# base.net
KiCad netlist of a schematic drawn in Altium Designer
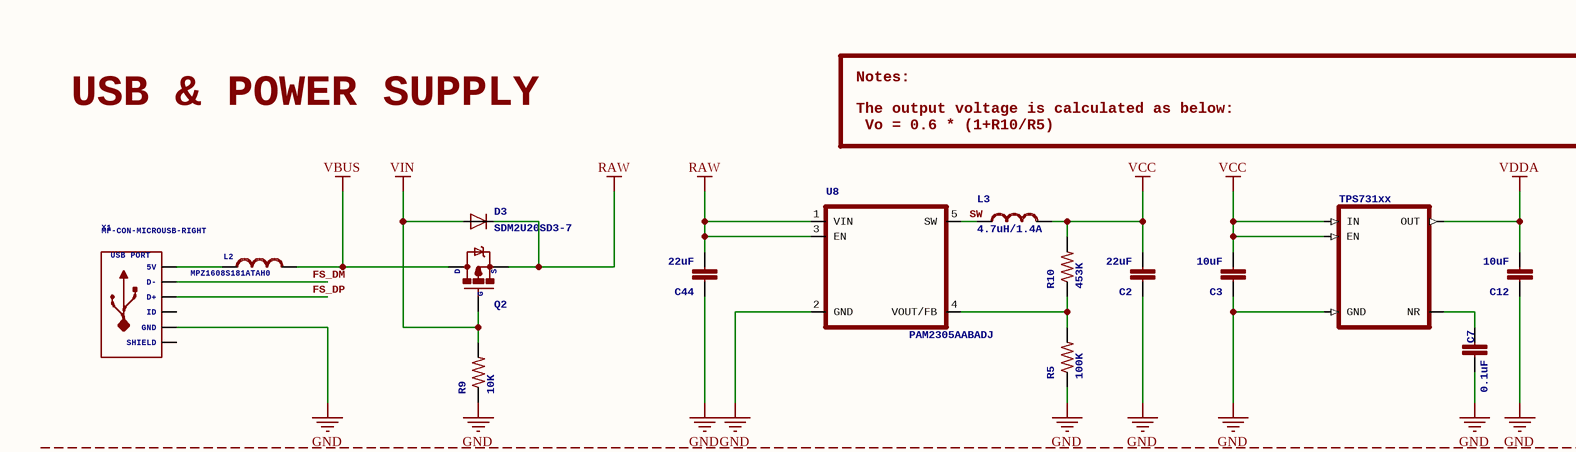
[diagram p0: base.SchDoc, top left]
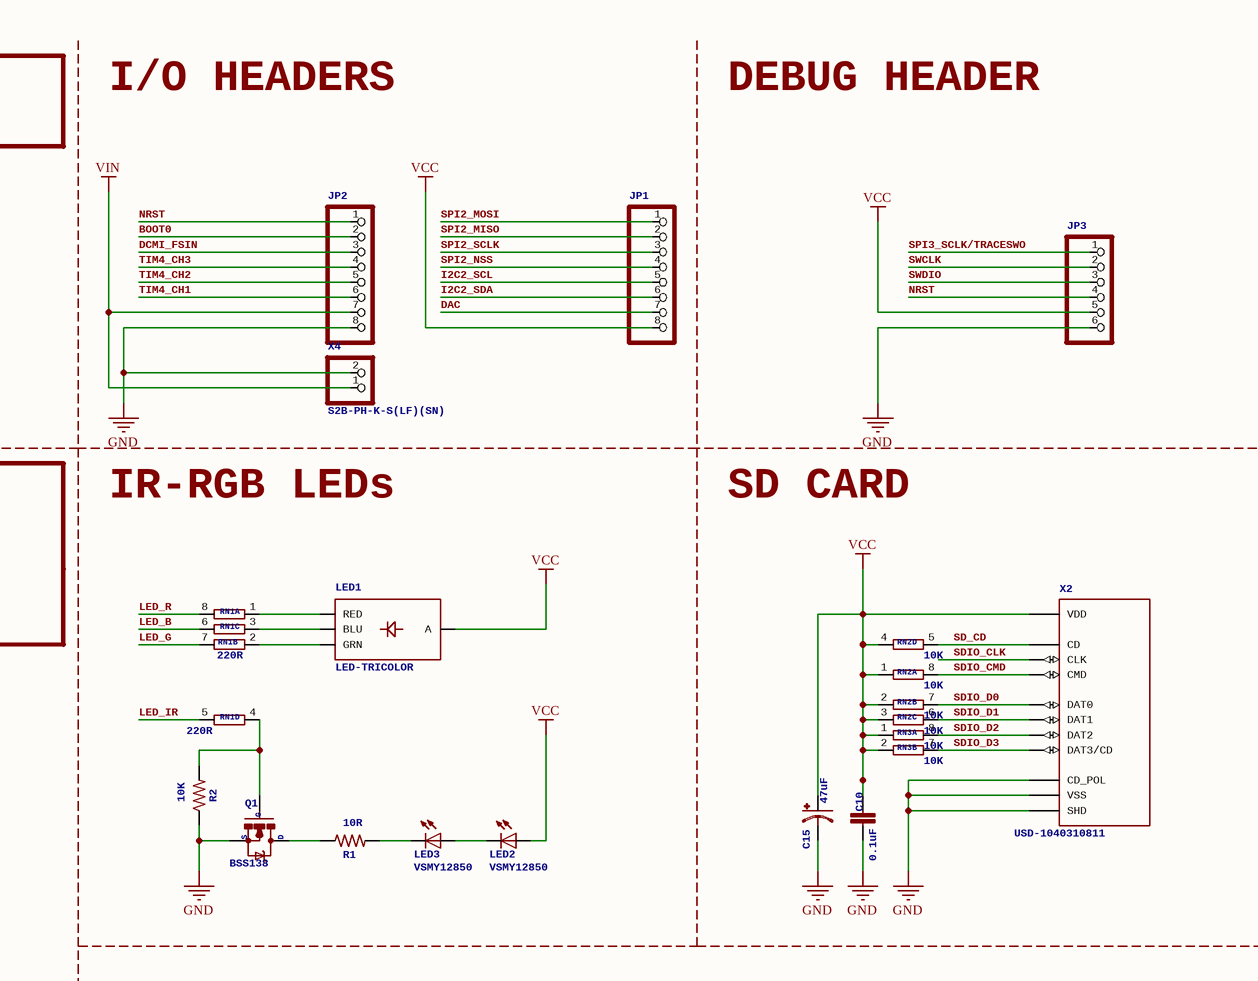
[diagram p1: base.SchDoc, top right]
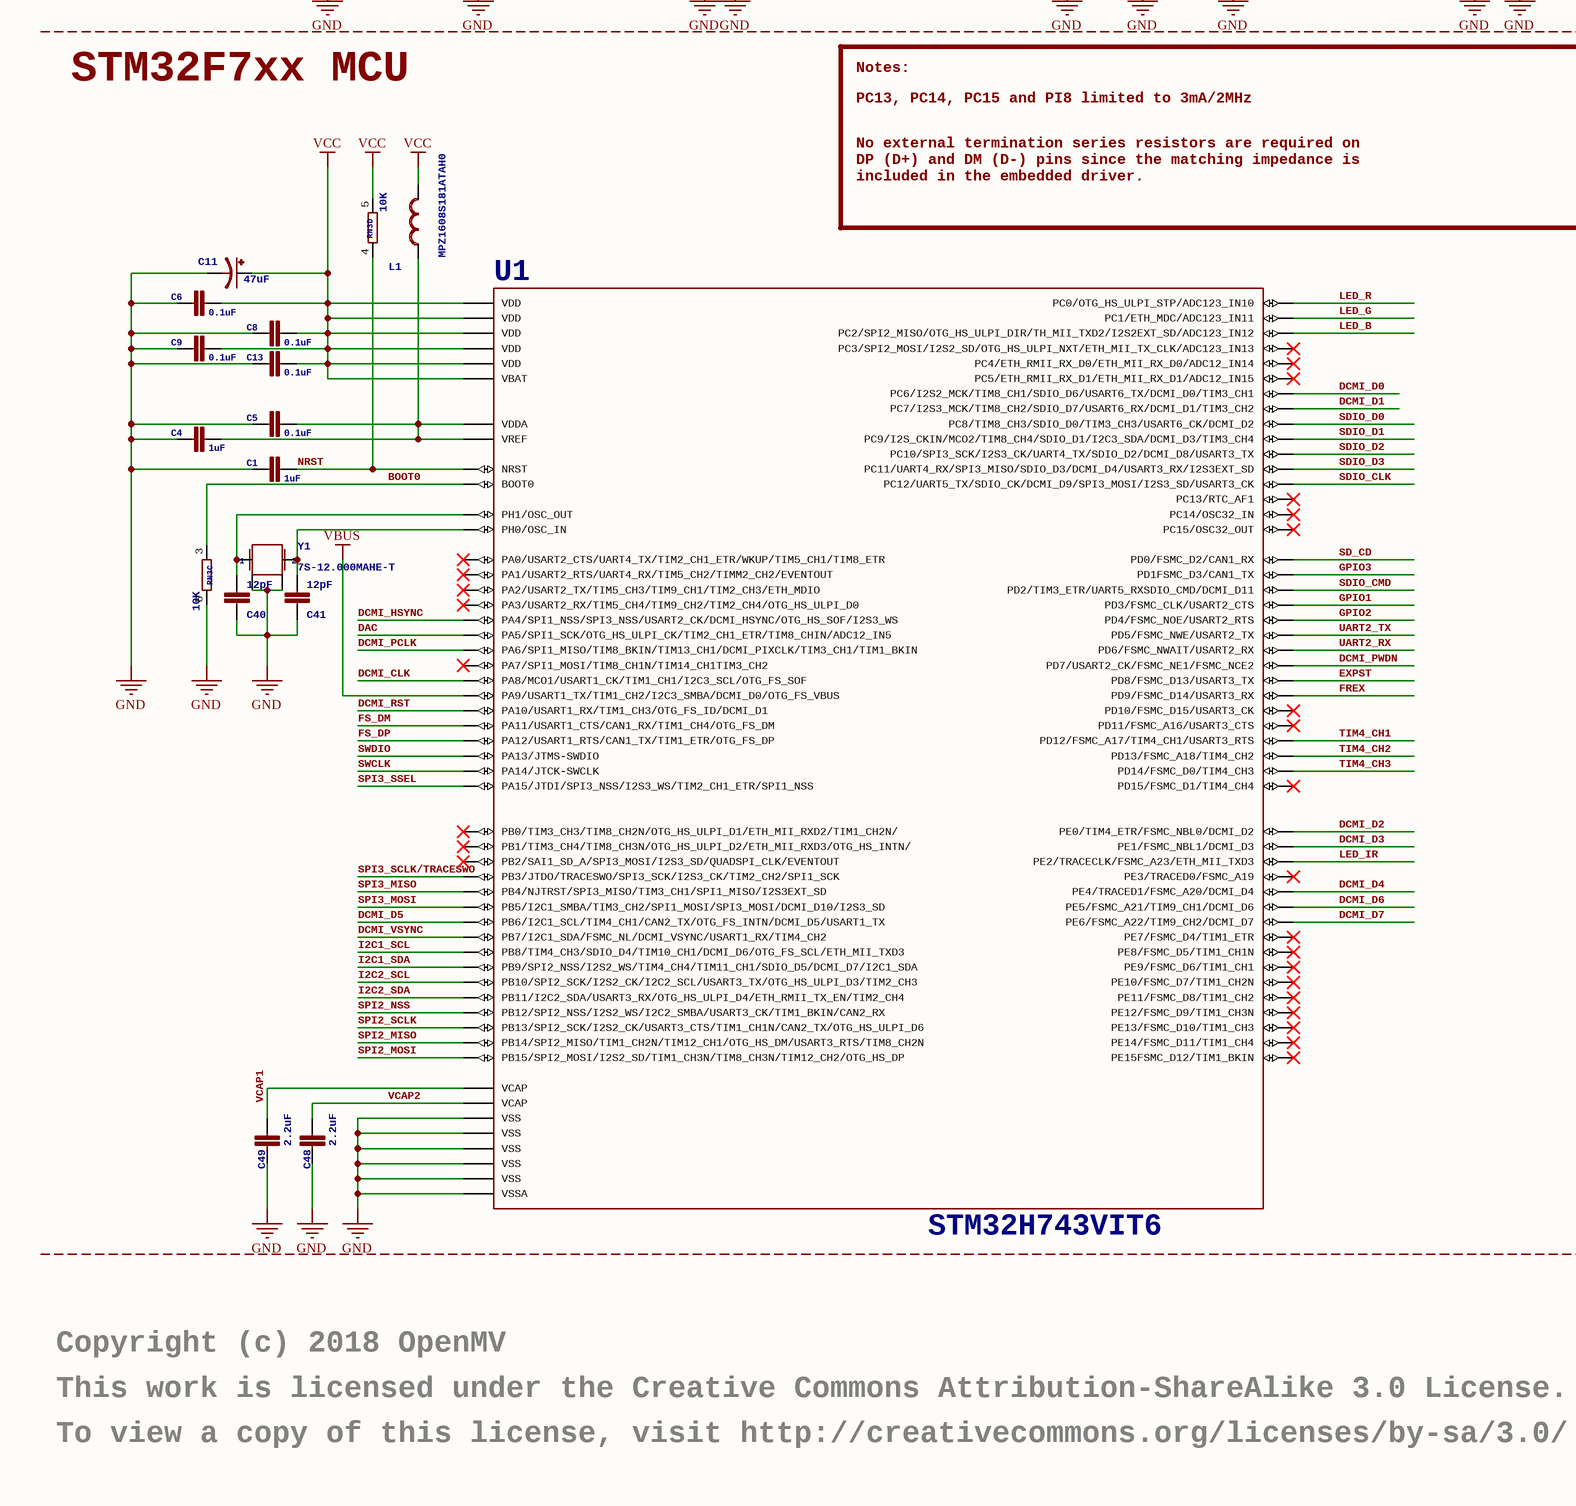
[diagram p2: base.SchDoc, bottom left]
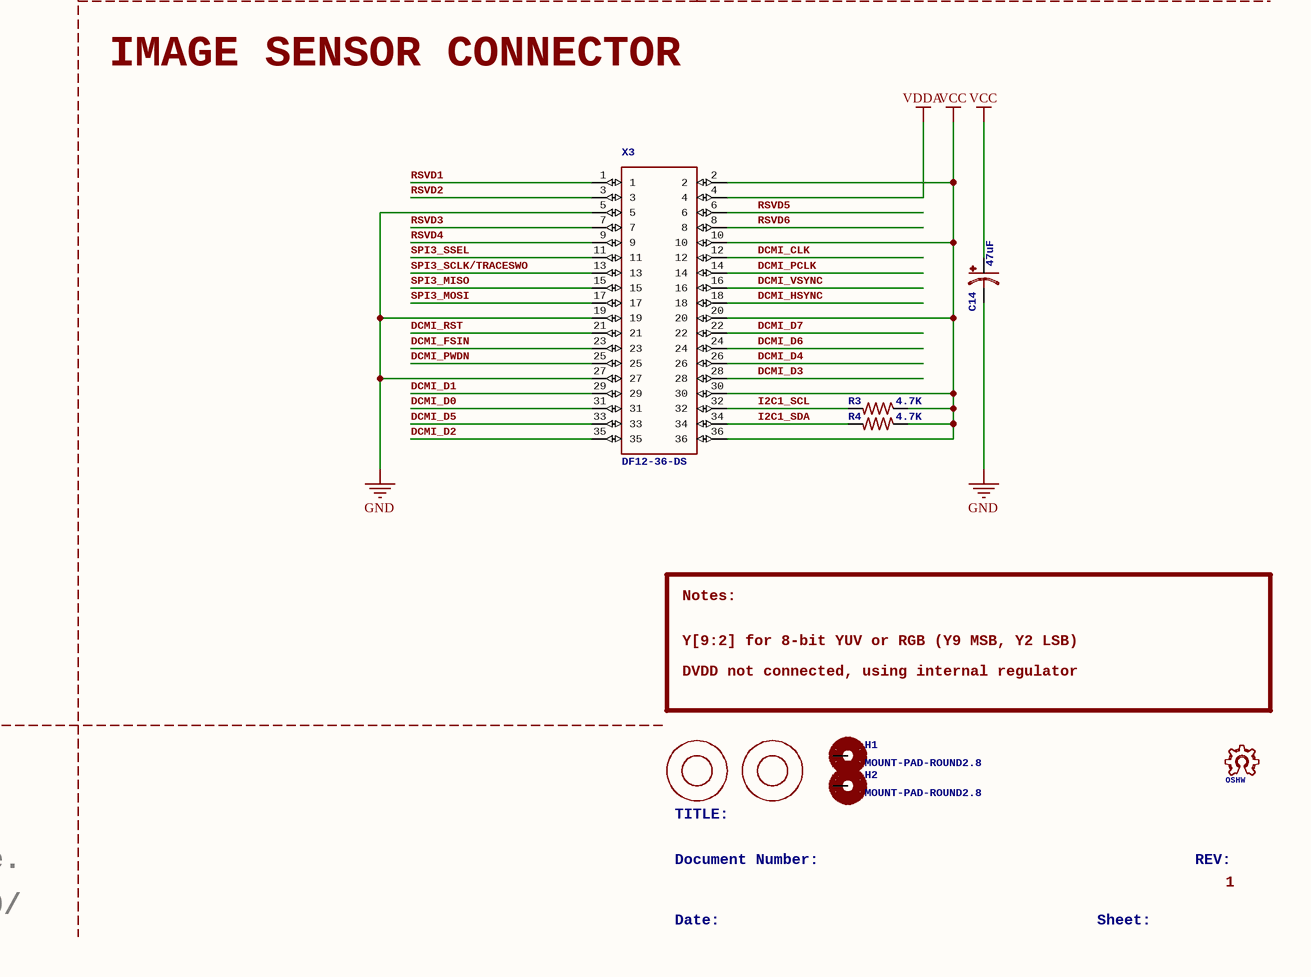
[diagram p3: base.SchDoc, bottom right]

(export (version "E")
  (design (tool "Eeschema 10.0.6"))
  (components
    (comp (ref "C1")
      (value "1uF")
      (footprint "0603-CAP")
      (description "CapacitorStandard 0603 ceramic capacitor, and 0.1\" leaded capacitor.")
      (libsource (lib "") (part "CAP0603-CAP_1"))
    )
    (comp (ref "C2")
      (value "22uF")
      (footprint "0805")
      (description "CapacitorStandard 0603 ceramic capacitor, and 0.1\" leaded capacitor.")
      (libsource (lib "sfe") (part "CAP0805"))
    )
    (comp (ref "C3")
      (value "10uF")
      (footprint "0805")
      (description "CapacitorStandard 0603 ceramic capacitor, and 0.1\" leaded capacitor.")
      (libsource (lib "sfe") (part "CAP0805"))
    )
    (comp (ref "C4")
      (value "1uF")
      (footprint "0603-CAP")
      (description "CapacitorStandard 0603 ceramic capacitor, and 0.1\" leaded capacitor.")
      (libsource (lib "") (part "CAP0603-CAP_1"))
    )
    (comp (ref "C5")
      (value "0.1uF")
      (footprint "0603-CAP")
      (description "CapacitorStandard 0603 ceramic capacitor, and 0.1\" leaded capacitor.")
      (libsource (lib "") (part "CAP0603-CAP_1"))
    )
    (comp (ref "C6")
      (value "0.1uF")
      (footprint "0603-CAP")
      (description "CapacitorStandard 0603 ceramic capacitor, and 0.1\" leaded capacitor.")
      (libsource (lib "") (part "CAP0603-CAP_1"))
    )
    (comp (ref "C7")
      (value "0.1uF")
      (footprint "0603-CAP")
      (description "CapacitorStandard 0603 ceramic capacitor, and 0.1\" leaded capacitor.")
      (libsource (lib "sfe") (part "CAP0603-CAP"))
    )
    (comp (ref "C8")
      (value "0.1uF")
      (footprint "0603-CAP")
      (description "CapacitorStandard 0603 ceramic capacitor, and 0.1\" leaded capacitor.")
      (libsource (lib "") (part "CAP0603-CAP_1"))
    )
    (comp (ref "C9")
      (value "0.1uF")
      (footprint "0603-CAP")
      (description "CapacitorStandard 0603 ceramic capacitor, and 0.1\" leaded capacitor.")
      (libsource (lib "") (part "CAP0603-CAP_1"))
    )
    (comp (ref "C10")
      (value "0.1uF")
      (footprint "0603-CAP")
      (description "CapacitorStandard 0603 ceramic capacitor, and 0.1\" leaded capacitor.")
      (libsource (lib "sfe") (part "CAP0603-CAP"))
    )
    (comp (ref "C11") (value "47uF") (footprint "EIA3216") (libsource (lib "") (part "CAP_POL1206_1")))
    (comp (ref "C12")
      (value "10uF")
      (footprint "0805")
      (description "CapacitorStandard 0603 ceramic capacitor, and 0.1\" leaded capacitor.")
      (libsource (lib "sfe") (part "CAP0805"))
    )
    (comp (ref "C13")
      (value "0.1uF")
      (footprint "0603-CAP")
      (description "CapacitorStandard 0603 ceramic capacitor, and 0.1\" leaded capacitor.")
      (libsource (lib "") (part "CAP0603-CAP_1"))
    )
    (comp (ref "C14") (value "47uF") (footprint "EIA3216") (libsource (lib "sfe") (part "CAP_POL1206")))
    (comp (ref "C15") (value "47uF") (footprint "EIA3216") (libsource (lib "sfe") (part "CAP_POL1206")))
    (comp (ref "C40")
      (value "12pF")
      (footprint "0603-CAP")
      (description "CapacitorStandard 0603 ceramic capacitor, and 0.1\" leaded capacitor.")
      (libsource (lib "") (part "CAP0603-CAP_2"))
    )
    (comp (ref "C41")
      (value "12pF")
      (footprint "0603-CAP")
      (description "CapacitorStandard 0603 ceramic capacitor, and 0.1\" leaded capacitor.")
      (libsource (lib "") (part "CAP0603-CAP_2"))
    )
    (comp (ref "C44")
      (value "22uF")
      (footprint "0805")
      (description "CapacitorStandard 0603 ceramic capacitor, and 0.1\" leaded capacitor.")
      (libsource (lib "sfe") (part "CAP0805"))
    )
    (comp (ref "C48")
      (value "2.2uF")
      (footprint "0603-CAP")
      (description "CapacitorStandard 0603 ceramic capacitor, and 0.1\" leaded capacitor.")
      (libsource (lib "sfe") (part "CAP0603-CAP"))
    )
    (comp (ref "C49")
      (value "2.2uF")
      (footprint "0603-CAP")
      (description "CapacitorStandard 0603 ceramic capacitor, and 0.1\" leaded capacitor.")
      (libsource (lib "sfe") (part "CAP0603-CAP"))
    )
    (comp (ref "D3") (value "SDM2U20SD3-7") (footprint "SOD-323") (libsource (lib "sfe") (part "DIODESOD")))
    (comp (ref "H1")
      (value "MOUNT-PAD-ROUND2.8")
      (footprint "2,8-PAD")
      (description "MOUNTING PAD, round")
      (libsource (lib "holes") (part "MOUNT-PAD-ROUND2.8"))
    )
    (comp (ref "H2")
      (value "MOUNT-PAD-ROUND2.8")
      (footprint "2,8-PAD")
      (description "MOUNTING PAD, round")
      (libsource (lib "holes") (part "MOUNT-PAD-ROUND2.8"))
    )
    (comp (ref "JP1")
      (value "PINHD-1X8")
      (footprint "1X08")
      (description "PIN HEADER")
      (fields (field (name "LIBRARYNAME") "pinhead"))
      (libsource (lib "pinhead") (part "PINHD-1X8"))
    )
    (comp (ref "JP2")
      (value "PINHD-1X8")
      (footprint "1X08")
      (description "PIN HEADER")
      (fields (field (name "LIBRARYNAME") "pinhead"))
      (libsource (lib "pinhead") (part "PINHD-1X8"))
    )
    (comp (ref "JP3")
      (value "PINHD-1X6")
      (footprint "1X06")
      (description "PIN HEADER")
      (fields (field (name "LIBRARYNAME") "pinhead"))
      (libsource (lib "pinhead") (part "PINHD-1X6"))
    )
    (comp (ref "L1")
      (value "MPZ1608S181ATAH0")
      (footprint "0603")
      (libsource (lib "sfe") (part "INDUCTOR0603"))
    )
    (comp (ref "L2")
      (value "MPZ1608S181ATAH0")
      (footprint "0603")
      (libsource (lib "sfe") (part "INDUCTOR0603"))
    )
    (comp (ref "L3") (value "4.7uH/1.4A") (footprint "1007") (libsource (lib "sfe") (part "INDUCTOR1007")))
    (comp (ref "LED1")
      (value "LED-TRICOLOR")
      (footprint "LED-TRICOLOR-SMD-MF")
      (libsource (lib "sfe") (part "LED-TRICOLOR"))
    )
    (comp (ref "LED2") (value "VSMY12850") (footprint "LED-1206") (libsource (lib "sfe") (part "LED1206")))
    (comp (ref "LED3") (value "VSMY12850") (footprint "LED-1206") (libsource (lib "sfe") (part "LED1206")))
    (comp (ref "LOGO1")
      (value "OSHW_LOGO_FILLX0100-NT")
      (footprint "OSHW_FILLX100_NOTEXT")
      (fields (field (name "OSHW") "OSHW") (field (name "LIBRARYNAME") "iofault"))
      (libsource (lib "iofault") (part "OSHW_LOGO_FILLX0100-NT"))
    )
    (comp (ref "M1")
      (value "9774030243R")
      (footprint "9774030151R")
      (libsource (lib "STANDOFFS") (part "9774030151R"))
    )
    (comp (ref "M2")
      (value "9774030243R")
      (footprint "9774030151R")
      (libsource (lib "STANDOFFS") (part "9774030151R"))
    )
    (comp (ref "Q1")
      (value "BSS138")
      (footprint "SOT23-3")
      (fields (field (name "D") "D") (field (name "S") "S") (field (name "G") "G"))
      (libsource (lib "sfe") (part "MOSFET-NCHANNELSMD"))
    )
    (comp (ref "Q2")
      (value "Si2301BDS")
      (footprint "SOT23-3")
      (fields (field (name "D") "D") (field (name "S") "S") (field (name "G") "G"))
      (libsource (lib "sfe") (part "MOSFET-PCHANNELSMD"))
    )
    (comp (ref "R1")
      (value "10R")
      (footprint "0603-RES")
      (description "ResistorBasic schematic elements and footprints for 0603, 1206, and PTH resistors.")
      (libsource (lib "sfe") (part "RESISTOR0603-RES"))
    )
    (comp (ref "R2")
      (value "10K")
      (footprint "0603-RES")
      (description "ResistorBasic schematic elements and footprints for 0603, 1206, and PTH resistors.")
      (libsource (lib "sfe") (part "RESISTOR0603-RES"))
    )
    (comp (ref "R3")
      (value "4.7K")
      (footprint "0603-RES")
      (description "ResistorBasic schematic elements and footprints for 0603, 1206, and PTH resistors.")
      (libsource (lib "sfe") (part "RESISTOR0603-RES"))
    )
    (comp (ref "R4")
      (value "4.7K")
      (footprint "0603-RES")
      (description "ResistorBasic schematic elements and footprints for 0603, 1206, and PTH resistors.")
      (libsource (lib "sfe") (part "RESISTOR0603-RES"))
    )
    (comp (ref "R5")
      (value "100K")
      (footprint "0603-RES")
      (description "ResistorBasic schematic elements and footprints for 0603, 1206, and PTH resistors.")
      (libsource (lib "sfe") (part "RESISTOR0603-RES"))
    )
    (comp (ref "R9")
      (value "10K")
      (footprint "0603-RES")
      (description "ResistorBasic schematic elements and footprints for 0603, 1206, and PTH resistors.")
      (libsource (lib "sfe") (part "RESISTOR0603-RES"))
    )
    (comp (ref "R10")
      (value "453K")
      (footprint "0603-RES")
      (description "ResistorBasic schematic elements and footprints for 0603, 1206, and PTH resistors.")
      (libsource (lib "sfe") (part "RESISTOR0603-RES"))
    )
    (comp (ref "RN1")
      (value "220R")
      (footprint "EXBV8V")
      (description "Array Chip Resistor   Source: RS Component / Phycomp")
      (fields (field (name "LIBRARYNAME") "resistor-dil"))
      (libsource (lib "resistor-dil") (part "4R-NEXBV8V"))
    )
    (comp (ref "RN2")
      (value "10K")
      (footprint "EXBV8V")
      (description "Array Chip Resistor   Source: RS Component / Phycomp")
      (fields (field (name "LIBRARYNAME") "resistor-dil"))
      (libsource (lib "resistor-dil") (part "4R-NEXBV8V"))
    )
    (comp (ref "RN3")
      (value "10K")
      (footprint "EXBV8V")
      (description "Array Chip Resistor   Source: RS Component / Phycomp")
      (fields (field (name "LIBRARYNAME") "resistor-dil"))
      (libsource (lib "resistor-dil") (part "4R-NEXBV8V"))
    )
    (comp (ref "U1")
      (value "STM32H743VIT6")
      (footprint "LQFP100")
      (libsource (lib "stm32") (part "STM32F746LQFP100"))
    )
    (comp (ref "U5")
      (value "TPS731XX")
      (footprint "SOT23-5")
      (fields (field (name "TPS731XX") "TPS731xx") (field (name "LIBRARYNAME") "mux"))
      (libsource (lib "mux") (part "TPS731XX"))
    )
    (comp (ref "U8")
      (value "PAM2305AABADJ")
      (footprint "TSOT25")
      (libsource (lib "regulators") (part "PAM2305AAB330"))
    )
    (comp (ref "X1")
      (value "MF-CON-MICROUSB-RIGHT")
      (footprint "MICROUSB-RIGHT")
      (fields
        (field (name "USBPORT") "USB PORT")
        (field (name "5V") "5V")
        (field (name "D-") "D-")
        (field (name "D+") "D+")
        (field (name "ID") "ID")
        (field (name "GND") "GND")
        (field (name "SHIELD") "SHIELD")
      )
      (libsource (lib "MF_Connectors") (part "USB_MICRO_RIGHT"))
    )
    (comp (ref "X2")
      (value "USD-1040310811")
      (footprint "1040310811")
      (libsource (lib "molex") (part "USD-1040310811"))
    )
    (comp (ref "X3")
      (value "DF12-36-DS")
      (footprint "DF12-36-DS")
      (libsource (lib "DF12") (part "DF12-36-DS"))
    )
    (comp (ref "X4")
      (value "S2B-PH-K-S(LF)(SN)")
      (footprint "JST-PH-2-THM-RA")
      (fields (field (name "LIBRARYNAME") "adafruit-updated"))
      (libsource (lib "adafruit-updated") (part "JST_2PIN-THM-RA"))
    )
    (comp (ref "Y1")
      (value "7S-12.000MAHE-T")
      (footprint "CRYSTAL-2.5X2.0")
      (description "CrystalsVarious standard crystals. Proven footprints. Spark Fun Electronics SKU : COM-00534")
      (fields (field (name "1") "1") (field (name "2") "2") (field (name "LIBRARYNAME") "mux"))
      (libsource (lib "mux") (part "CRYSTAL2.5X2.0"))
    )
  )
  (nets
    (net (code "1") (name "/BOOT0") (class "Default")
      (node (ref "JP2") (pin "2") (pinfunction "2_2") (pintype "passive"))
      (node (ref "RN3") (pin "3") (pinfunction "1_3") (pintype "passive"))
      (node (ref "U1") (pin "94") (pinfunction "BOOT0_94") (pintype "bidirectional"))
    )
    (net (code "2") (name "/DAC") (class "Default")
      (node (ref "JP1") (pin "7") (pinfunction "7_7") (pintype "passive"))
      (node (ref "U1") (pin "29") (pinfunction "PA5/SPI1_SCK/OTG_HS_ULPI_CK/TIM2_CH1_ETR/TIM8_CHIN/ADC12_IN5_29") (pintype "bidirectional"))
    )
    (net (code "3") (name "/DCMI_CLK") (class "Default")
      (node (ref "U1") (pin "67") (pinfunction "PA8/MCO1/USART1_CK/TIM1_CH1/I2C3_SCL/OTG_FS_SOF_67") (pintype "bidirectional"))
      (node (ref "X3") (pin "12") (pinfunction "12_12") (pintype "bidirectional"))
    )
    (net (code "4") (name "/DCMI_D0") (class "Default")
      (node (ref "U1") (pin "63") (pinfunction "PC6/I2S2_MCK/TIM8_CH1/SDIO_D6/USART6_TX/DCMI_D0/TIM3_CH1_63") (pintype "bidirectional"))
      (node (ref "X3") (pin "31") (pinfunction "31_31") (pintype "bidirectional"))
    )
    (net (code "5") (name "/DCMI_D1") (class "Default")
      (node (ref "U1") (pin "64") (pinfunction "PC7/I2S3_MCK/TIM8_CH2/SDIO_D7/USART6_RX/DCMI_D1/TIM3_CH2_64") (pintype "bidirectional"))
      (node (ref "X3") (pin "29") (pinfunction "29_29") (pintype "bidirectional"))
    )
    (net (code "6") (name "/DCMI_D2") (class "Default")
      (node (ref "U1") (pin "97") (pinfunction "PE0/TIM4_ETR/FSMC_NBL0/DCMI_D2_97") (pintype "bidirectional"))
      (node (ref "X3") (pin "35") (pinfunction "35_35") (pintype "bidirectional"))
    )
    (net (code "7") (name "/DCMI_D3") (class "Default")
      (node (ref "U1") (pin "98") (pinfunction "PE1/FSMC_NBL1/DCMI_D3_98") (pintype "bidirectional"))
      (node (ref "X3") (pin "28") (pinfunction "28_28") (pintype "bidirectional"))
    )
    (net (code "8") (name "/DCMI_D4") (class "Default")
      (node (ref "U1") (pin "3") (pinfunction "PE4/TRACED1/FSMC_A20/DCMI_D4_3") (pintype "bidirectional"))
      (node (ref "X3") (pin "26") (pinfunction "26_26") (pintype "bidirectional"))
    )
    (net (code "9") (name "/DCMI_D5") (class "Default")
      (node (ref "U1") (pin "92") (pinfunction "PB6/I2C1_SCL/TIM4_CH1/CAN2_TX/OTG_FS_INTN/DCMI_D5/USART1_TX_92") (pintype "bidirectional"))
      (node (ref "X3") (pin "33") (pinfunction "33_33") (pintype "bidirectional"))
    )
    (net (code "10") (name "/DCMI_D6") (class "Default")
      (node (ref "U1") (pin "4") (pinfunction "PE5/FSMC_A21/TIM9_CH1/DCMI_D6_4") (pintype "bidirectional"))
      (node (ref "X3") (pin "24") (pinfunction "24_24") (pintype "bidirectional"))
    )
    (net (code "11") (name "/DCMI_D7") (class "Default")
      (node (ref "U1") (pin "5") (pinfunction "PE6/FSMC_A22/TIM9_CH2/DCMI_D7_5") (pintype "bidirectional"))
      (node (ref "X3") (pin "22") (pinfunction "22_22") (pintype "bidirectional"))
    )
    (net (code "12") (name "/DCMI_FSIN") (class "Default")
      (node (ref "JP2") (pin "3") (pinfunction "3_3") (pintype "passive"))
      (node (ref "X3") (pin "23") (pinfunction "23_23") (pintype "bidirectional"))
    )
    (net (code "13") (name "/DCMI_HSYNC") (class "Default")
      (node (ref "U1") (pin "28") (pinfunction "PA4/SPI1_NSS/SPI3_NSS/USART2_CK/DCMI_HSYNC/OTG_HS_SOF/I2S3_WS_28") (pintype "bidirectional"))
      (node (ref "X3") (pin "18") (pinfunction "18_18") (pintype "bidirectional"))
    )
    (net (code "14") (name "/DCMI_PCLK") (class "Default")
      (node (ref "U1") (pin "30") (pinfunction "PA6/SPI1_MISO/TIM8_BKIN/TIM13_CH1/DCMI_PIXCLK/TIM3_CH1/TIM1_BKIN_30") (pintype "bidirectional"))
      (node (ref "X3") (pin "14") (pinfunction "14_14") (pintype "bidirectional"))
    )
    (net (code "15") (name "/DCMI_PWDN") (class "Default")
      (node (ref "U1") (pin "88") (pinfunction "PD7/USART2_CK/FSMC_NE1/FSMC_NCE2_88") (pintype "bidirectional"))
      (node (ref "X3") (pin "25") (pinfunction "25_25") (pintype "bidirectional"))
    )
    (net (code "16") (name "/DCMI_RST") (class "Default")
      (node (ref "U1") (pin "69") (pinfunction "PA10/USART1_RX/TIM1_CH3/OTG_FS_ID/DCMI_D1_69") (pintype "bidirectional"))
      (node (ref "X3") (pin "21") (pinfunction "21_21") (pintype "bidirectional"))
    )
    (net (code "17") (name "/DCMI_VSYNC") (class "Default")
      (node (ref "U1") (pin "93") (pinfunction "PB7/I2C1_SDA/FSMC_NL/DCMI_VSYNC/USART1_RX/TIM4_CH2_93") (pintype "bidirectional"))
      (node (ref "X3") (pin "16") (pinfunction "16_16") (pintype "bidirectional"))
    )
    (net (code "18") (name "/EXPST") (class "Default")
      (node (ref "U1") (pin "55") (pinfunction "PD8/FSMC_D13/USART3_TX_55") (pintype "bidirectional"))
    )
    (net (code "19") (name "/FREX") (class "Default")
      (node (ref "U1") (pin "56") (pinfunction "PD9/FSMC_D14/USART3_RX_56") (pintype "bidirectional"))
    )
    (net (code "20") (name "/FS_DM") (class "Default")
      (node (ref "U1") (pin "70") (pinfunction "PA11/USART1_CTS/CAN1_RX/TIM1_CH4/OTG_FS_DM_70") (pintype "bidirectional"))
      (node (ref "X1") (pin "2") (pinfunction "D-_2") (pintype "bidirectional"))
    )
    (net (code "21") (name "/FS_DP") (class "Default")
      (node (ref "U1") (pin "71") (pinfunction "PA12/USART1_RTS/CAN1_TX/TIM1_ETR/OTG_FS_DP_71") (pintype "bidirectional"))
      (node (ref "X1") (pin "3") (pinfunction "D+_3") (pintype "bidirectional"))
    )
    (net (code "22") (name "/GPIO1") (class "Default")
      (node (ref "U1") (pin "84") (pinfunction "PD3/FSMC_CLK/USART2_CTS_84") (pintype "bidirectional"))
    )
    (net (code "23") (name "/GPIO2") (class "Default")
      (node (ref "U1") (pin "85") (pinfunction "PD4/FSMC_NOE/USART2_RTS_85") (pintype "bidirectional"))
    )
    (net (code "24") (name "/GPIO3") (class "Default")
      (node (ref "U1") (pin "82") (pinfunction "PD1FSMC_D3/CAN1_TX_82") (pintype "bidirectional"))
    )
    (net (code "25") (name "/I2C1_SCL") (class "Default")
      (node (ref "R3") (pin "2") (pinfunction "2_2") (pintype "passive"))
      (node (ref "U1") (pin "95") (pinfunction "PB8/TIM4_CH3/SDIO_D4/TIM10_CH1/DCMI_D6/OTG_FS_SCL/ETH_MII_TXD3_95") (pintype "bidirectional"))
      (node (ref "X3") (pin "32") (pinfunction "32_32") (pintype "bidirectional"))
    )
    (net (code "26") (name "/I2C1_SDA") (class "Default")
      (node (ref "R4") (pin "2") (pinfunction "2_2") (pintype "passive"))
      (node (ref "U1") (pin "96") (pinfunction "PB9/SPI2_NSS/I2S2_WS/TIM4_CH4/TIM11_CH1/SDIO_D5/DCMI_D7/I2C1_SDA_96") (pintype "bidirectional"))
      (node (ref "X3") (pin "34") (pinfunction "34_34") (pintype "bidirectional"))
    )
    (net (code "27") (name "/I2C2_SCL") (class "Default")
      (node (ref "JP1") (pin "5") (pinfunction "5_5") (pintype "passive"))
      (node (ref "U1") (pin "46") (pinfunction "PB10/SPI2_SCK/I2S2_CK/I2C2_SCL/USART3_TX/OTG_HS_ULPI_D3/TIM2_CH3_46") (pintype "bidirectional"))
    )
    (net (code "28") (name "/I2C2_SDA") (class "Default")
      (node (ref "JP1") (pin "6") (pinfunction "6_6") (pintype "passive"))
      (node (ref "U1") (pin "47") (pinfunction "PB11/I2C2_SDA/USART3_RX/OTG_HS_ULPI_D4/ETH_RMII_TX_EN/TIM2_CH4_47") (pintype "bidirectional"))
    )
    (net (code "29") (name "/LED_B") (class "Default")
      (node (ref "RN1") (pin "6") (pinfunction "2_6") (pintype "passive"))
      (node (ref "U1") (pin "17") (pinfunction "PC2/SPI2_MISO/OTG_HS_ULPI_DIR/TH_MII_TXD2/I2S2EXT_SD/ADC123_IN12_17") (pintype "bidirectional"))
    )
    (net (code "30") (name "/LED_G") (class "Default")
      (node (ref "RN1") (pin "7") (pinfunction "2_7") (pintype "passive"))
      (node (ref "U1") (pin "16") (pinfunction "PC1/ETH_MDC/ADC123_IN11_16") (pintype "bidirectional"))
    )
    (net (code "31") (name "/LED_IR") (class "Default")
      (node (ref "RN1") (pin "5") (pinfunction "2_5") (pintype "passive"))
      (node (ref "U1") (pin "1") (pinfunction "PE2/TRACECLK/FSMC_A23/ETH_MII_TXD3_1") (pintype "bidirectional"))
    )
    (net (code "32") (name "/LED_R") (class "Default")
      (node (ref "RN1") (pin "8") (pinfunction "2_8") (pintype "passive"))
      (node (ref "U1") (pin "15") (pinfunction "PC0/OTG_HS_ULPI_STP/ADC123_IN10_15") (pintype "bidirectional"))
    )
    (net (code "33") (name "/NRST") (class "Default")
      (node (ref "C1") (pin "1") (pinfunction "1_1") (pintype "passive"))
      (node (ref "JP2") (pin "1") (pinfunction "1_1") (pintype "passive"))
      (node (ref "JP3") (pin "4") (pinfunction "4_4") (pintype "passive"))
      (node (ref "RN3") (pin "4") (pinfunction "1_4") (pintype "passive"))
      (node (ref "U1") (pin "14") (pinfunction "NRST_14") (pintype "bidirectional"))
    )
    (net (code "34") (name "/RSVD1") (class "Default")
      (node (ref "X3") (pin "1") (pinfunction "1_1") (pintype "bidirectional"))
    )
    (net (code "35") (name "/RSVD2") (class "Default")
      (node (ref "X3") (pin "3") (pinfunction "3_3") (pintype "bidirectional"))
    )
    (net (code "36") (name "/RSVD3") (class "Default")
      (node (ref "X3") (pin "7") (pinfunction "7_7") (pintype "bidirectional"))
    )
    (net (code "37") (name "/RSVD4") (class "Default")
      (node (ref "X3") (pin "9") (pinfunction "9_9") (pintype "bidirectional"))
    )
    (net (code "38") (name "/RSVD5") (class "Default")
      (node (ref "X3") (pin "6") (pinfunction "6_6") (pintype "bidirectional"))
    )
    (net (code "39") (name "/RSVD6") (class "Default")
      (node (ref "X3") (pin "8") (pinfunction "8_8") (pintype "bidirectional"))
    )
    (net (code "40") (name "/SDIO_CLK") (class "Default")
      (node (ref "U1") (pin "80") (pinfunction "PC12/UART5_TX/SDIO_CK/DCMI_D9/SPI3_MOSI/I2S3_SD/USART3_CK_80") (pintype "bidirectional"))
      (node (ref "X2") (pin "P$5") (pinfunction "CLK_P$5") (pintype "bidirectional"))
    )
    (net (code "41") (name "/SDIO_CMD") (class "Default")
      (node (ref "RN2") (pin "8") (pinfunction "2_8") (pintype "passive"))
      (node (ref "U1") (pin "83") (pinfunction "PD2/TIM3_ETR/UART5_RXSDIO_CMD/DCMI_D11_83") (pintype "bidirectional"))
      (node (ref "X2") (pin "P$3") (pinfunction "CMD_P$3") (pintype "bidirectional"))
    )
    (net (code "42") (name "/SDIO_D0") (class "Default")
      (node (ref "RN2") (pin "7") (pinfunction "2_7") (pintype "passive"))
      (node (ref "U1") (pin "65") (pinfunction "PC8/TIM8_CH3/SDIO_D0/TIM3_CH3/USART6_CK/DCMI_D2_65") (pintype "bidirectional"))
      (node (ref "X2") (pin "P$7") (pinfunction "DAT0_P$7") (pintype "bidirectional"))
    )
    (net (code "43") (name "/SDIO_D1") (class "Default")
      (node (ref "RN2") (pin "6") (pinfunction "2_6") (pintype "passive"))
      (node (ref "U1") (pin "66") (pinfunction "PC9/I2S_CKIN/MCO2/TIM8_CH4/SDIO_D1/I2C3_SDA/DCMI_D3/TIM3_CH4_66") (pintype "bidirectional"))
      (node (ref "X2") (pin "P$8") (pinfunction "DAT1_P$8") (pintype "bidirectional"))
    )
    (net (code "44") (name "/SDIO_D2") (class "Default")
      (node (ref "RN3") (pin "8") (pinfunction "2_8") (pintype "passive"))
      (node (ref "U1") (pin "78") (pinfunction "PC10/SPI3_SCK/I2S3_CK/UART4_TX/SDIO_D2/DCMI_D8/USART3_TX_78") (pintype "bidirectional"))
      (node (ref "X2") (pin "P$1") (pinfunction "DAT2_P$1") (pintype "bidirectional"))
    )
    (net (code "45") (name "/SDIO_D3") (class "Default")
      (node (ref "RN3") (pin "7") (pinfunction "2_7") (pintype "passive"))
      (node (ref "U1") (pin "79") (pinfunction "PC11/UART4_RX/SPI3_MISO/SDIO_D3/DCMI_D4/USART3_RX/I2S3EXT_SD_79") (pintype "bidirectional"))
      (node (ref "X2") (pin "P$2") (pinfunction "DAT3/CD_P$2") (pintype "bidirectional"))
    )
    (net (code "46") (name "/SD_CD") (class "Default")
      (node (ref "RN2") (pin "5") (pinfunction "2_5") (pintype "passive"))
      (node (ref "U1") (pin "81") (pinfunction "PD0/FSMC_D2/CAN1_RX_81") (pintype "bidirectional"))
      (node (ref "X2") (pin "CD$1") (pinfunction "CD_CD$1") (pintype "power_in"))
    )
    (net (code "47") (name "/SPI2_MISO") (class "Default")
      (node (ref "JP1") (pin "2") (pinfunction "2_2") (pintype "passive"))
      (node (ref "U1") (pin "53") (pinfunction "PB14/SPI2_MISO/TIM1_CH2N/TIM12_CH1/OTG_HS_DM/USART3_RTS/TIM8_CH2N_53") (pintype "bidirectional"))
    )
    (net (code "48") (name "/SPI2_MOSI") (class "Default")
      (node (ref "JP1") (pin "1") (pinfunction "1_1") (pintype "passive"))
      (node (ref "U1") (pin "54") (pinfunction "PB15/SPI2_MOSI/I2S2_SD/TIM1_CH3N/TIM8_CH3N/TIM12_CH2/OTG_HS_DP_54") (pintype "bidirectional"))
    )
    (net (code "49") (name "/SPI2_NSS") (class "Default")
      (node (ref "JP1") (pin "4") (pinfunction "4_4") (pintype "passive"))
      (node (ref "U1") (pin "51") (pinfunction "PB12/SPI2_NSS/I2S2_WS/I2C2_SMBA/USART3_CK/TIM1_BKIN/CAN2_RX_51") (pintype "bidirectional"))
    )
    (net (code "50") (name "/SPI2_SCLK") (class "Default")
      (node (ref "JP1") (pin "3") (pinfunction "3_3") (pintype "passive"))
      (node (ref "U1") (pin "52") (pinfunction "PB13/SPI2_SCK/I2S2_CK/USART3_CTS/TIM1_CH1N/CAN2_TX/OTG_HS_ULPI_D6_52") (pintype "bidirectional"))
    )
    (net (code "51") (name "/SPI3_MISO") (class "Default")
      (node (ref "U1") (pin "90") (pinfunction "PB4/NJTRST/SPI3_MISO/TIM3_CH1/SPI1_MISO/I2S3EXT_SD_90") (pintype "bidirectional"))
      (node (ref "X3") (pin "15") (pinfunction "15_15") (pintype "bidirectional"))
    )
    (net (code "52") (name "/SPI3_MOSI") (class "Default")
      (node (ref "U1") (pin "91") (pinfunction "PB5/I2C1_SMBA/TIM3_CH2/SPI1_MOSI/SPI3_MOSI/DCMI_D10/I2S3_SD_91") (pintype "bidirectional"))
      (node (ref "X3") (pin "17") (pinfunction "17_17") (pintype "bidirectional"))
    )
    (net (code "53") (name "/SPI3_SCLK{slash}TRACESWO") (class "Default")
      (node (ref "JP3") (pin "1") (pinfunction "1_1") (pintype "passive"))
      (node (ref "U1") (pin "89") (pinfunction "PB3/JTDO/TRACESWO/SPI3_SCK/I2S3_CK/TIM2_CH2/SPI1_SCK_89") (pintype "bidirectional"))
      (node (ref "X3") (pin "13") (pinfunction "13_13") (pintype "bidirectional"))
    )
    (net (code "54") (name "/SPI3_SSEL") (class "Default")
      (node (ref "U1") (pin "77") (pinfunction "PA15/JTDI/SPI3_NSS/I2S3_WS/TIM2_CH1_ETR/SPI1_NSS_77") (pintype "bidirectional"))
      (node (ref "X3") (pin "11") (pinfunction "11_11") (pintype "bidirectional"))
    )
    (net (code "55") (name "/SW") (class "Default")
      (node (ref "L3") (pin "1") (pinfunction "1_1") (pintype "passive"))
      (node (ref "U8") (pin "5") (pinfunction "SW_5") (pintype "power_in"))
    )
    (net (code "56") (name "/SWCLK") (class "Default")
      (node (ref "JP3") (pin "2") (pinfunction "2_2") (pintype "passive"))
      (node (ref "U1") (pin "76") (pinfunction "PA14/JTCK-SWCLK_76") (pintype "bidirectional"))
    )
    (net (code "57") (name "/SWDIO") (class "Default")
      (node (ref "JP3") (pin "3") (pinfunction "3_3") (pintype "passive"))
      (node (ref "U1") (pin "72") (pinfunction "PA13/JTMS-SWDIO_72") (pintype "bidirectional"))
    )
    (net (code "58") (name "/TIM4_CH1") (class "Default")
      (node (ref "JP2") (pin "6") (pinfunction "6_6") (pintype "passive"))
      (node (ref "U1") (pin "59") (pinfunction "PD12/FSMC_A17/TIM4_CH1/USART3_RTS_59") (pintype "bidirectional"))
    )
    (net (code "59") (name "/TIM4_CH2") (class "Default")
      (node (ref "JP2") (pin "5") (pinfunction "5_5") (pintype "passive"))
      (node (ref "U1") (pin "60") (pinfunction "PD13/FSMC_A18/TIM4_CH2_60") (pintype "bidirectional"))
    )
    (net (code "60") (name "/TIM4_CH3") (class "Default")
      (node (ref "JP2") (pin "4") (pinfunction "4_4") (pintype "passive"))
      (node (ref "U1") (pin "61") (pinfunction "PD14/FSMC_D0/TIM4_CH3_61") (pintype "bidirectional"))
    )
    (net (code "61") (name "/UART2_RX") (class "Default")
      (node (ref "U1") (pin "87") (pinfunction "PD6/FSMC_NWAIT/USART2_RX_87") (pintype "bidirectional"))
    )
    (net (code "62") (name "/UART2_TX") (class "Default")
      (node (ref "U1") (pin "86") (pinfunction "PD5/FSMC_NWE/USART2_TX_86") (pintype "bidirectional"))
    )
    (net (code "63") (name "/VCAP1") (class "Default")
      (node (ref "C49") (pin "1") (pinfunction "1_1") (pintype "passive"))
      (node (ref "U1") (pin "48") (pinfunction "VCAP_48") (pintype "power_in"))
    )
    (net (code "64") (name "/VCAP2") (class "Default")
      (node (ref "C48") (pin "1") (pinfunction "1_1") (pintype "passive"))
      (node (ref "U1") (pin "73") (pinfunction "VCAP_73") (pintype "power_in"))
    )
    (net (code "65") (name "GND") (class "Default")
      (node (ref "C1") (pin "2") (pinfunction "2_2") (pintype "passive"))
      (node (ref "C10") (pin "2") (pinfunction "2_2") (pintype "passive"))
      (node (ref "C11") (pin "C") (pinfunction "-_C") (pintype "passive"))
      (node (ref "C12") (pin "1") (pinfunction "1_1") (pintype "passive"))
      (node (ref "C13") (pin "2") (pinfunction "2_2") (pintype "passive"))
      (node (ref "C14") (pin "C") (pinfunction "-_C") (pintype "passive"))
      (node (ref "C15") (pin "C") (pinfunction "-_C") (pintype "passive"))
      (node (ref "C2") (pin "1") (pinfunction "1_1") (pintype "passive"))
      (node (ref "C3") (pin "1") (pinfunction "1_1") (pintype "passive"))
      (node (ref "C4") (pin "2") (pinfunction "2_2") (pintype "passive"))
      (node (ref "C40") (pin "1") (pinfunction "1_1") (pintype "passive"))
      (node (ref "C41") (pin "1") (pinfunction "1_1") (pintype "passive"))
      (node (ref "C44") (pin "1") (pinfunction "1_1") (pintype "passive"))
      (node (ref "C48") (pin "2") (pinfunction "2_2") (pintype "passive"))
      (node (ref "C49") (pin "2") (pinfunction "2_2") (pintype "passive"))
      (node (ref "C5") (pin "2") (pinfunction "2_2") (pintype "passive"))
      (node (ref "C6") (pin "2") (pinfunction "2_2") (pintype "passive"))
      (node (ref "C7") (pin "2") (pinfunction "2_2") (pintype "passive"))
      (node (ref "C8") (pin "2") (pinfunction "2_2") (pintype "passive"))
      (node (ref "C9") (pin "2") (pinfunction "2_2") (pintype "passive"))
      (node (ref "JP2") (pin "8") (pinfunction "8_8") (pintype "passive"))
      (node (ref "JP3") (pin "6") (pinfunction "6_6") (pintype "passive"))
      (node (ref "Q1") (pin "2") (pinfunction "S_2") (pintype "passive"))
      (node (ref "R2") (pin "1") (pinfunction "1_1") (pintype "passive"))
      (node (ref "R5") (pin "1") (pinfunction "1_1") (pintype "passive"))
      (node (ref "R9") (pin "1") (pinfunction "1_1") (pintype "passive"))
      (node (ref "RN3") (pin "6") (pinfunction "2_6") (pintype "passive"))
      (node (ref "U1") (pin "10") (pinfunction "VSS_10") (pintype "power_in"))
      (node (ref "U1") (pin "19") (pinfunction "VSSA_19") (pintype "power_in"))
      (node (ref "U1") (pin "26") (pinfunction "VSS_26") (pintype "power_in"))
      (node (ref "U1") (pin "49") (pinfunction "VSS_49") (pintype "power_in"))
      (node (ref "U1") (pin "74") (pinfunction "VSS_74") (pintype "power_in"))
      (node (ref "U1") (pin "99") (pinfunction "VSS_99") (pintype "power_in"))
      (node (ref "U5") (pin "2") (pinfunction "GND_2") (pintype "input"))
      (node (ref "U8") (pin "2") (pinfunction "GND_2") (pintype "power_in"))
      (node (ref "X1") (pin "5") (pinfunction "GND_5") (pintype "power_in"))
      (node (ref "X2") (pin "CD$2") (pinfunction "CD_POL_CD$2") (pintype "power_in"))
      (node (ref "X2") (pin "G$1_G$2_G$3_G$4") (pinfunction "SHD_G$1_G$2_G$3_G$4") (pintype "power_in"))
      (node (ref "X2") (pin "P$6") (pinfunction "VSS_P$6") (pintype "power_in"))
      (node (ref "X3") (pin "19") (pinfunction "19_19") (pintype "bidirectional"))
      (node (ref "X3") (pin "27") (pinfunction "27_27") (pintype "bidirectional"))
      (node (ref "X3") (pin "5") (pinfunction "5_5") (pintype "bidirectional"))
      (node (ref "X4") (pin "2") (pinfunction "1_2") (pintype "passive"))
      (node (ref "Y1") (pin "2") (pinfunction "P$1_2") (pintype "power_in"))
      (node (ref "Y1") (pin "4") (pinfunction "P$2_4") (pintype "power_in"))
    )
    (net (code "66") (name "Net-(LED1-BLU)") (class "Default")
      (node (ref "LED1") (pin "B") (pinfunction "BLU_B") (pintype "bidirectional"))
      (node (ref "RN1") (pin "3") (pinfunction "1_3") (pintype "passive"))
    )
    (net (code "67") (name "Net-(LED1-GRN)") (class "Default")
      (node (ref "LED1") (pin "G") (pinfunction "GRN_G") (pintype "bidirectional"))
      (node (ref "RN1") (pin "2") (pinfunction "1_2") (pintype "passive"))
    )
    (net (code "68") (name "Net-(LED1-RED)") (class "Default")
      (node (ref "LED1") (pin "R") (pinfunction "RED_R") (pintype "bidirectional"))
      (node (ref "RN1") (pin "1") (pinfunction "1_1") (pintype "passive"))
    )
    (net (code "69") (name "Net-(LED2-PadC)") (class "Default")
      (node (ref "LED2") (pin "C") (pinfunction "C_C") (pintype "passive"))
      (node (ref "LED3") (pin "A") (pinfunction "A_A") (pintype "passive"))
    )
    (net (code "70") (name "Net-(LED3-PadC)") (class "Default")
      (node (ref "LED3") (pin "C") (pinfunction "C_C") (pintype "passive"))
      (node (ref "R1") (pin "2") (pinfunction "2_2") (pintype "passive"))
    )
    (net (code "71") (name "Net-(Q1-D)") (class "Default")
      (node (ref "Q1") (pin "3") (pinfunction "D_3") (pintype "passive"))
      (node (ref "R1") (pin "1") (pinfunction "1_1") (pintype "passive"))
    )
    (net (code "72") (name "Net-(Q1-G)") (class "Default")
      (node (ref "Q1") (pin "1") (pinfunction "G_1") (pintype "passive"))
      (node (ref "R2") (pin "2") (pinfunction "2_2") (pintype "passive"))
      (node (ref "RN1") (pin "4") (pinfunction "1_4") (pintype "passive"))
    )
    (net (code "73") (name "Net-(U1-PH0{slash}OSC_IN)") (class "Default")
      (node (ref "C41") (pin "2") (pinfunction "2_2") (pintype "passive"))
      (node (ref "U1") (pin "12") (pinfunction "PH0/OSC_IN_12") (pintype "bidirectional"))
      (node (ref "Y1") (pin "1") (pinfunction "1_1") (pintype "passive"))
    )
    (net (code "74") (name "Net-(U1-PH1{slash}OSC_OUT)") (class "Default")
      (node (ref "C40") (pin "2") (pinfunction "2_2") (pintype "passive"))
      (node (ref "U1") (pin "13") (pinfunction "PH1/OSC_OUT_13") (pintype "bidirectional"))
      (node (ref "Y1") (pin "3") (pinfunction "2_3") (pintype "passive"))
    )
    (net (code "75") (name "Net-(U1-VDDA)") (class "Default")
      (node (ref "C4") (pin "1") (pinfunction "1_1") (pintype "passive"))
      (node (ref "C5") (pin "1") (pinfunction "1_1") (pintype "passive"))
      (node (ref "L1") (pin "1") (pinfunction "1_1") (pintype "passive"))
      (node (ref "U1") (pin "20") (pinfunction "VREF_20") (pintype "power_in"))
      (node (ref "U1") (pin "21") (pinfunction "VDDA_21") (pintype "power_in"))
    )
    (net (code "76") (name "Net-(U5-NR)") (class "Default")
      (node (ref "C7") (pin "1") (pinfunction "1_1") (pintype "passive"))
      (node (ref "U5") (pin "4") (pinfunction "NR_4") (pintype "passive"))
    )
    (net (code "77") (name "Net-(U8-VOUT{slash}FB)") (class "Default")
      (node (ref "R10") (pin "1") (pinfunction "1_1") (pintype "passive"))
      (node (ref "R5") (pin "2") (pinfunction "2_2") (pintype "passive"))
      (node (ref "U8") (pin "4") (pinfunction "VOUT/FB_4") (pintype "passive"))
    )
    (net (code "78") (name "Net-(X1-5V)") (class "Default")
      (node (ref "L2") (pin "1") (pinfunction "1_1") (pintype "passive"))
      (node (ref "X1") (pin "1") (pinfunction "5V_1") (pintype "power_in"))
    )
    (net (code "79") (name "RAW") (class "Default")
      (node (ref "C44") (pin "2") (pinfunction "2_2") (pintype "passive"))
      (node (ref "D3") (pin "1") (pinfunction "C_1") (pintype "passive"))
      (node (ref "Q2") (pin "2") (pinfunction "S_2") (pintype "passive"))
      (node (ref "U8") (pin "1") (pinfunction "VIN_1") (pintype "power_in"))
      (node (ref "U8") (pin "3") (pinfunction "EN_3") (pintype "passive"))
    )
    (net (code "80") (name "VBUS") (class "Default")
      (node (ref "L2") (pin "2") (pinfunction "2_2") (pintype "passive"))
      (node (ref "Q2") (pin "3") (pinfunction "D_3") (pintype "passive"))
      (node (ref "U1") (pin "68") (pinfunction "PA9/USART1_TX/TIM1_CH2/I2C3_SMBA/DCMI_D0/OTG_FS_VBUS_68") (pintype "bidirectional"))
    )
    (net (code "81") (name "VCC") (class "Default")
      (node (ref "C10") (pin "1") (pinfunction "1_1") (pintype "passive"))
      (node (ref "C11") (pin "A") (pinfunction "+_A") (pintype "passive"))
      (node (ref "C13") (pin "1") (pinfunction "1_1") (pintype "passive"))
      (node (ref "C14") (pin "A") (pinfunction "+_A") (pintype "passive"))
      (node (ref "C15") (pin "A") (pinfunction "+_A") (pintype "passive"))
      (node (ref "C2") (pin "2") (pinfunction "2_2") (pintype "passive"))
      (node (ref "C3") (pin "2") (pinfunction "2_2") (pintype "passive"))
      (node (ref "C6") (pin "1") (pinfunction "1_1") (pintype "passive"))
      (node (ref "C8") (pin "1") (pinfunction "1_1") (pintype "passive"))
      (node (ref "C9") (pin "1") (pinfunction "1_1") (pintype "passive"))
      (node (ref "JP1") (pin "8") (pinfunction "8_8") (pintype "passive"))
      (node (ref "JP3") (pin "5") (pinfunction "5_5") (pintype "passive"))
      (node (ref "L1") (pin "2") (pinfunction "2_2") (pintype "passive"))
      (node (ref "L3") (pin "2") (pinfunction "2_2") (pintype "passive"))
      (node (ref "LED1") (pin "A") (pinfunction "A_A") (pintype "bidirectional"))
      (node (ref "LED2") (pin "A") (pinfunction "A_A") (pintype "passive"))
      (node (ref "R10") (pin "2") (pinfunction "2_2") (pintype "passive"))
      (node (ref "R3") (pin "1") (pinfunction "1_1") (pintype "passive"))
      (node (ref "R4") (pin "1") (pinfunction "1_1") (pintype "passive"))
      (node (ref "RN2") (pin "1") (pinfunction "1_1") (pintype "passive"))
      (node (ref "RN2") (pin "2") (pinfunction "1_2") (pintype "passive"))
      (node (ref "RN2") (pin "3") (pinfunction "1_3") (pintype "passive"))
      (node (ref "RN2") (pin "4") (pinfunction "1_4") (pintype "passive"))
      (node (ref "RN3") (pin "1") (pinfunction "1_1") (pintype "passive"))
      (node (ref "RN3") (pin "2") (pinfunction "1_2") (pintype "passive"))
      (node (ref "RN3") (pin "5") (pinfunction "2_5") (pintype "passive"))
      (node (ref "U1") (pin "100") (pinfunction "VDD_100") (pintype "power_in"))
      (node (ref "U1") (pin "11") (pinfunction "VDD_11") (pintype "power_in"))
      (node (ref "U1") (pin "27") (pinfunction "VDD_27") (pintype "power_in"))
      (node (ref "U1") (pin "50") (pinfunction "VDD_50") (pintype "power_in"))
      (node (ref "U1") (pin "6") (pinfunction "VBAT_6") (pintype "power_in"))
      (node (ref "U1") (pin "75") (pinfunction "VDD_75") (pintype "power_in"))
      (node (ref "U5") (pin "1") (pinfunction "IN_1") (pintype "input"))
      (node (ref "U5") (pin "3") (pinfunction "EN_3") (pintype "input"))
      (node (ref "X2") (pin "P$4") (pinfunction "VDD_P$4") (pintype "power_in"))
      (node (ref "X3") (pin "10") (pinfunction "10_10") (pintype "bidirectional"))
      (node (ref "X3") (pin "2") (pinfunction "2_2") (pintype "bidirectional"))
      (node (ref "X3") (pin "20") (pinfunction "20_20") (pintype "bidirectional"))
      (node (ref "X3") (pin "30") (pinfunction "30_30") (pintype "bidirectional"))
      (node (ref "X3") (pin "36") (pinfunction "36_36") (pintype "bidirectional"))
    )
    (net (code "82") (name "VDDA") (class "Default")
      (node (ref "C12") (pin "2") (pinfunction "2_2") (pintype "passive"))
      (node (ref "U5") (pin "5") (pinfunction "OUT_5") (pintype "output"))
      (node (ref "X3") (pin "4") (pinfunction "4_4") (pintype "bidirectional"))
    )
    (net (code "83") (name "VIN") (class "Default")
      (node (ref "D3") (pin "2") (pinfunction "A_2") (pintype "passive"))
      (node (ref "JP2") (pin "7") (pinfunction "7_7") (pintype "passive"))
      (node (ref "Q2") (pin "1") (pinfunction "G_1") (pintype "passive"))
      (node (ref "R9") (pin "2") (pinfunction "2_2") (pintype "passive"))
      (node (ref "X4") (pin "1") (pinfunction "2_1") (pintype "passive"))
    )
    (net (code "84") (name "unconnected-(H1-MOUNT-PadB2)") (class "Default")
      (node (ref "H1") (pin "B2") (pinfunction "MOUNT_B2") (pintype "passive"))
      (node (ref "H1") (pin "8") (pinfunction "MOUNT_8") (pintype "passive"))
    )
    (net (code "85") (name "unconnected-(H2-MOUNT-PadB2)") (class "Default")
      (node (ref "H2") (pin "B2") (pinfunction "MOUNT_B2") (pintype "passive"))
      (node (ref "H2") (pin "8") (pinfunction "MOUNT_8") (pintype "passive"))
    )
    (net (code "86") (name "unconnected-(U1-PA0{slash}USART2_CTS{slash}UART4_TX{slash}TIM2_CH1_ETR{slash}WKUP{slash}TIM5_CH1{slash}TIM8_ETR-Pad22)") (class "Default")
      (node (ref "U1") (pin "22") (pinfunction "PA0/USART2_CTS/UART4_TX/TIM2_CH1_ETR/WKUP/TIM5_CH1/TIM8_ETR_22") (pintype "bidirectional+no_connect"))
    )
    (net (code "87") (name "unconnected-(U1-PA1{slash}USART2_RTS{slash}UART4_RX{slash}TIM5_CH2{slash}TIMM2_CH2{slash}EVENTOUT-Pad23)") (class "Default")
      (node (ref "U1") (pin "23") (pinfunction "PA1/USART2_RTS/UART4_RX/TIM5_CH2/TIMM2_CH2/EVENTOUT_23") (pintype "bidirectional+no_connect"))
    )
    (net (code "88") (name "unconnected-(U1-PA2{slash}USART2_TX{slash}TIM5_CH3{slash}TIM9_CH1{slash}TIM2_CH3{slash}ETH_MDIO-Pad24)") (class "Default")
      (node (ref "U1") (pin "24") (pinfunction "PA2/USART2_TX/TIM5_CH3/TIM9_CH1/TIM2_CH3/ETH_MDIO_24") (pintype "bidirectional+no_connect"))
    )
    (net (code "89") (name "unconnected-(U1-PA3{slash}USART2_RX{slash}TIM5_CH4{slash}TIM9_CH2{slash}TIM2_CH4{slash}OTG_HS_ULPI_D0-Pad25)") (class "Default")
      (node (ref "U1") (pin "25") (pinfunction "PA3/USART2_RX/TIM5_CH4/TIM9_CH2/TIM2_CH4/OTG_HS_ULPI_D0_25") (pintype "bidirectional+no_connect"))
    )
    (net (code "90") (name "unconnected-(U1-PA7{slash}SPI1_MOSI{slash}TIM8_CH1N{slash}TIM14_CH1TIM3_CH2-Pad31)") (class "Default")
      (node (ref "U1") (pin "31") (pinfunction "PA7/SPI1_MOSI/TIM8_CH1N/TIM14_CH1TIM3_CH2_31") (pintype "bidirectional+no_connect"))
    )
    (net (code "91") (name "unconnected-(U1-PB0{slash}TIM3_CH3{slash}TIM8_CH2N{slash}OTG_HS_ULPI_D1{slash}ETH_MII_RXD2{slash}TIM1_CH2N{slash}-Pad34)") (class "Default")
      (node (ref "U1") (pin "34") (pinfunction "PB0/TIM3_CH3/TIM8_CH2N/OTG_HS_ULPI_D1/ETH_MII_RXD2/TIM1_CH2N/_34") (pintype "bidirectional+no_connect"))
    )
    (net (code "92") (name "unconnected-(U1-PB1{slash}TIM3_CH4{slash}TIM8_CH3N{slash}OTG_HS_ULPI_D2{slash}ETH_MII_RXD3{slash}OTG_HS_INTN{slash}-Pad35)") (class "Default")
      (node (ref "U1") (pin "35") (pinfunction "PB1/TIM3_CH4/TIM8_CH3N/OTG_HS_ULPI_D2/ETH_MII_RXD3/OTG_HS_INTN/_35") (pintype "bidirectional+no_connect"))
    )
    (net (code "93") (name "unconnected-(U1-PB2{slash}SAI1_SD_A{slash}SPI3_MOSI{slash}I2S3_SD{slash}QUADSPI_CLK{slash}EVENTOUT-Pad36)") (class "Default")
      (node (ref "U1") (pin "36") (pinfunction "PB2/SAI1_SD_A/SPI3_MOSI/I2S3_SD/QUADSPI_CLK/EVENTOUT_36") (pintype "bidirectional+no_connect"))
    )
    (net (code "94") (name "unconnected-(U1-PC3{slash}SPI2_MOSI{slash}I2S2_SD{slash}OTG_HS_ULPI_NXT{slash}ETH_MII_TX_CLK{slash}ADC123_IN13-Pad18)") (class "Default")
      (node (ref "U1") (pin "18") (pinfunction "PC3/SPI2_MOSI/I2S2_SD/OTG_HS_ULPI_NXT/ETH_MII_TX_CLK/ADC123_IN13_18") (pintype "bidirectional+no_connect"))
    )
    (net (code "95") (name "unconnected-(U1-PC4{slash}ETH_RMII_RX_D0{slash}ETH_MII_RX_D0{slash}ADC12_IN14-Pad32)") (class "Default")
      (node (ref "U1") (pin "32") (pinfunction "PC4/ETH_RMII_RX_D0/ETH_MII_RX_D0/ADC12_IN14_32") (pintype "bidirectional+no_connect"))
    )
    (net (code "96") (name "unconnected-(U1-PC5{slash}ETH_RMII_RX_D1{slash}ETH_MII_RX_D1{slash}ADC12_IN15-Pad33)") (class "Default")
      (node (ref "U1") (pin "33") (pinfunction "PC5/ETH_RMII_RX_D1/ETH_MII_RX_D1/ADC12_IN15_33") (pintype "bidirectional+no_connect"))
    )
    (net (code "97") (name "unconnected-(U1-PC13{slash}RTC_AF1-Pad7)") (class "Default")
      (node (ref "U1") (pin "7") (pinfunction "PC13/RTC_AF1_7") (pintype "bidirectional+no_connect"))
    )
    (net (code "98") (name "unconnected-(U1-PC14{slash}OSC32_IN-Pad8)") (class "Default")
      (node (ref "U1") (pin "8") (pinfunction "PC14/OSC32_IN_8") (pintype "bidirectional+no_connect"))
    )
    (net (code "99") (name "unconnected-(U1-PC15{slash}OSC32_OUT-Pad9)") (class "Default")
      (node (ref "U1") (pin "9") (pinfunction "PC15/OSC32_OUT_9") (pintype "bidirectional+no_connect"))
    )
    (net (code "100") (name "unconnected-(U1-PD10{slash}FSMC_D15{slash}USART3_CK-Pad57)") (class "Default")
      (node (ref "U1") (pin "57") (pinfunction "PD10/FSMC_D15/USART3_CK_57") (pintype "bidirectional+no_connect"))
    )
    (net (code "101") (name "unconnected-(U1-PD11{slash}FSMC_A16{slash}USART3_CTS-Pad58)") (class "Default")
      (node (ref "U1") (pin "58") (pinfunction "PD11/FSMC_A16/USART3_CTS_58") (pintype "bidirectional+no_connect"))
    )
    (net (code "102") (name "unconnected-(U1-PD15{slash}FSMC_D1{slash}TIM4_CH4-Pad62)") (class "Default")
      (node (ref "U1") (pin "62") (pinfunction "PD15/FSMC_D1/TIM4_CH4_62") (pintype "bidirectional+no_connect"))
    )
    (net (code "103") (name "unconnected-(U1-PE3{slash}TRACED0{slash}FSMC_A19-Pad2)") (class "Default")
      (node (ref "U1") (pin "2") (pinfunction "PE3/TRACED0/FSMC_A19_2") (pintype "bidirectional+no_connect"))
    )
    (net (code "104") (name "unconnected-(U1-PE7{slash}FSMC_D4{slash}TIM1_ETR-Pad37)") (class "Default")
      (node (ref "U1") (pin "37") (pinfunction "PE7/FSMC_D4/TIM1_ETR_37") (pintype "bidirectional+no_connect"))
    )
    (net (code "105") (name "unconnected-(U1-PE8{slash}FSMC_D5{slash}TIM1_CH1N-Pad38)") (class "Default")
      (node (ref "U1") (pin "38") (pinfunction "PE8/FSMC_D5/TIM1_CH1N_38") (pintype "bidirectional+no_connect"))
    )
    (net (code "106") (name "unconnected-(U1-PE9{slash}FSMC_D6{slash}TIM1_CH1-Pad39)") (class "Default")
      (node (ref "U1") (pin "39") (pinfunction "PE9/FSMC_D6/TIM1_CH1_39") (pintype "bidirectional+no_connect"))
    )
    (net (code "107") (name "unconnected-(U1-PE10{slash}FSMC_D7{slash}TIM1_CH2N-Pad40)") (class "Default")
      (node (ref "U1") (pin "40") (pinfunction "PE10/FSMC_D7/TIM1_CH2N_40") (pintype "bidirectional+no_connect"))
    )
    (net (code "108") (name "unconnected-(U1-PE11{slash}FSMC_D8{slash}TIM1_CH2-Pad41)") (class "Default")
      (node (ref "U1") (pin "41") (pinfunction "PE11/FSMC_D8/TIM1_CH2_41") (pintype "bidirectional+no_connect"))
    )
    (net (code "109") (name "unconnected-(U1-PE12{slash}FSMC_D9{slash}TIM1_CH3N-Pad42)") (class "Default")
      (node (ref "U1") (pin "42") (pinfunction "PE12/FSMC_D9/TIM1_CH3N_42") (pintype "bidirectional+no_connect"))
    )
    (net (code "110") (name "unconnected-(U1-PE13{slash}FSMC_D10{slash}TIM1_CH3-Pad43)") (class "Default")
      (node (ref "U1") (pin "43") (pinfunction "PE13/FSMC_D10/TIM1_CH3_43") (pintype "bidirectional+no_connect"))
    )
    (net (code "111") (name "unconnected-(U1-PE14{slash}FSMC_D11{slash}TIM1_CH4-Pad44)") (class "Default")
      (node (ref "U1") (pin "44") (pinfunction "PE14/FSMC_D11/TIM1_CH4_44") (pintype "bidirectional+no_connect"))
    )
    (net (code "112") (name "unconnected-(U1-PE15FSMC_D12{slash}TIM1_BKIN-Pad45)") (class "Default")
      (node (ref "U1") (pin "45") (pinfunction "PE15FSMC_D12/TIM1_BKIN_45") (pintype "bidirectional+no_connect"))
    )
    (net (code "113") (name "unconnected-(X1-ID-Pad4)") (class "Default")
      (node (ref "X1") (pin "4") (pinfunction "ID_4") (pintype "bidirectional"))
    )
    (net (code "114") (name "unconnected-(X1-SLD-PadS1_S2_S3_S4_S5_S6)") (class "Default")
      (node (ref "X1") (pin "S1_S2_S3_S4_S5_S6") (pinfunction "SLD_S1_S2_S3_S4_S5_S6") (pintype "passive"))
    )
  )
)
